# GongKong.net
KiCad netlist of a schematic drawn in Altium Designer
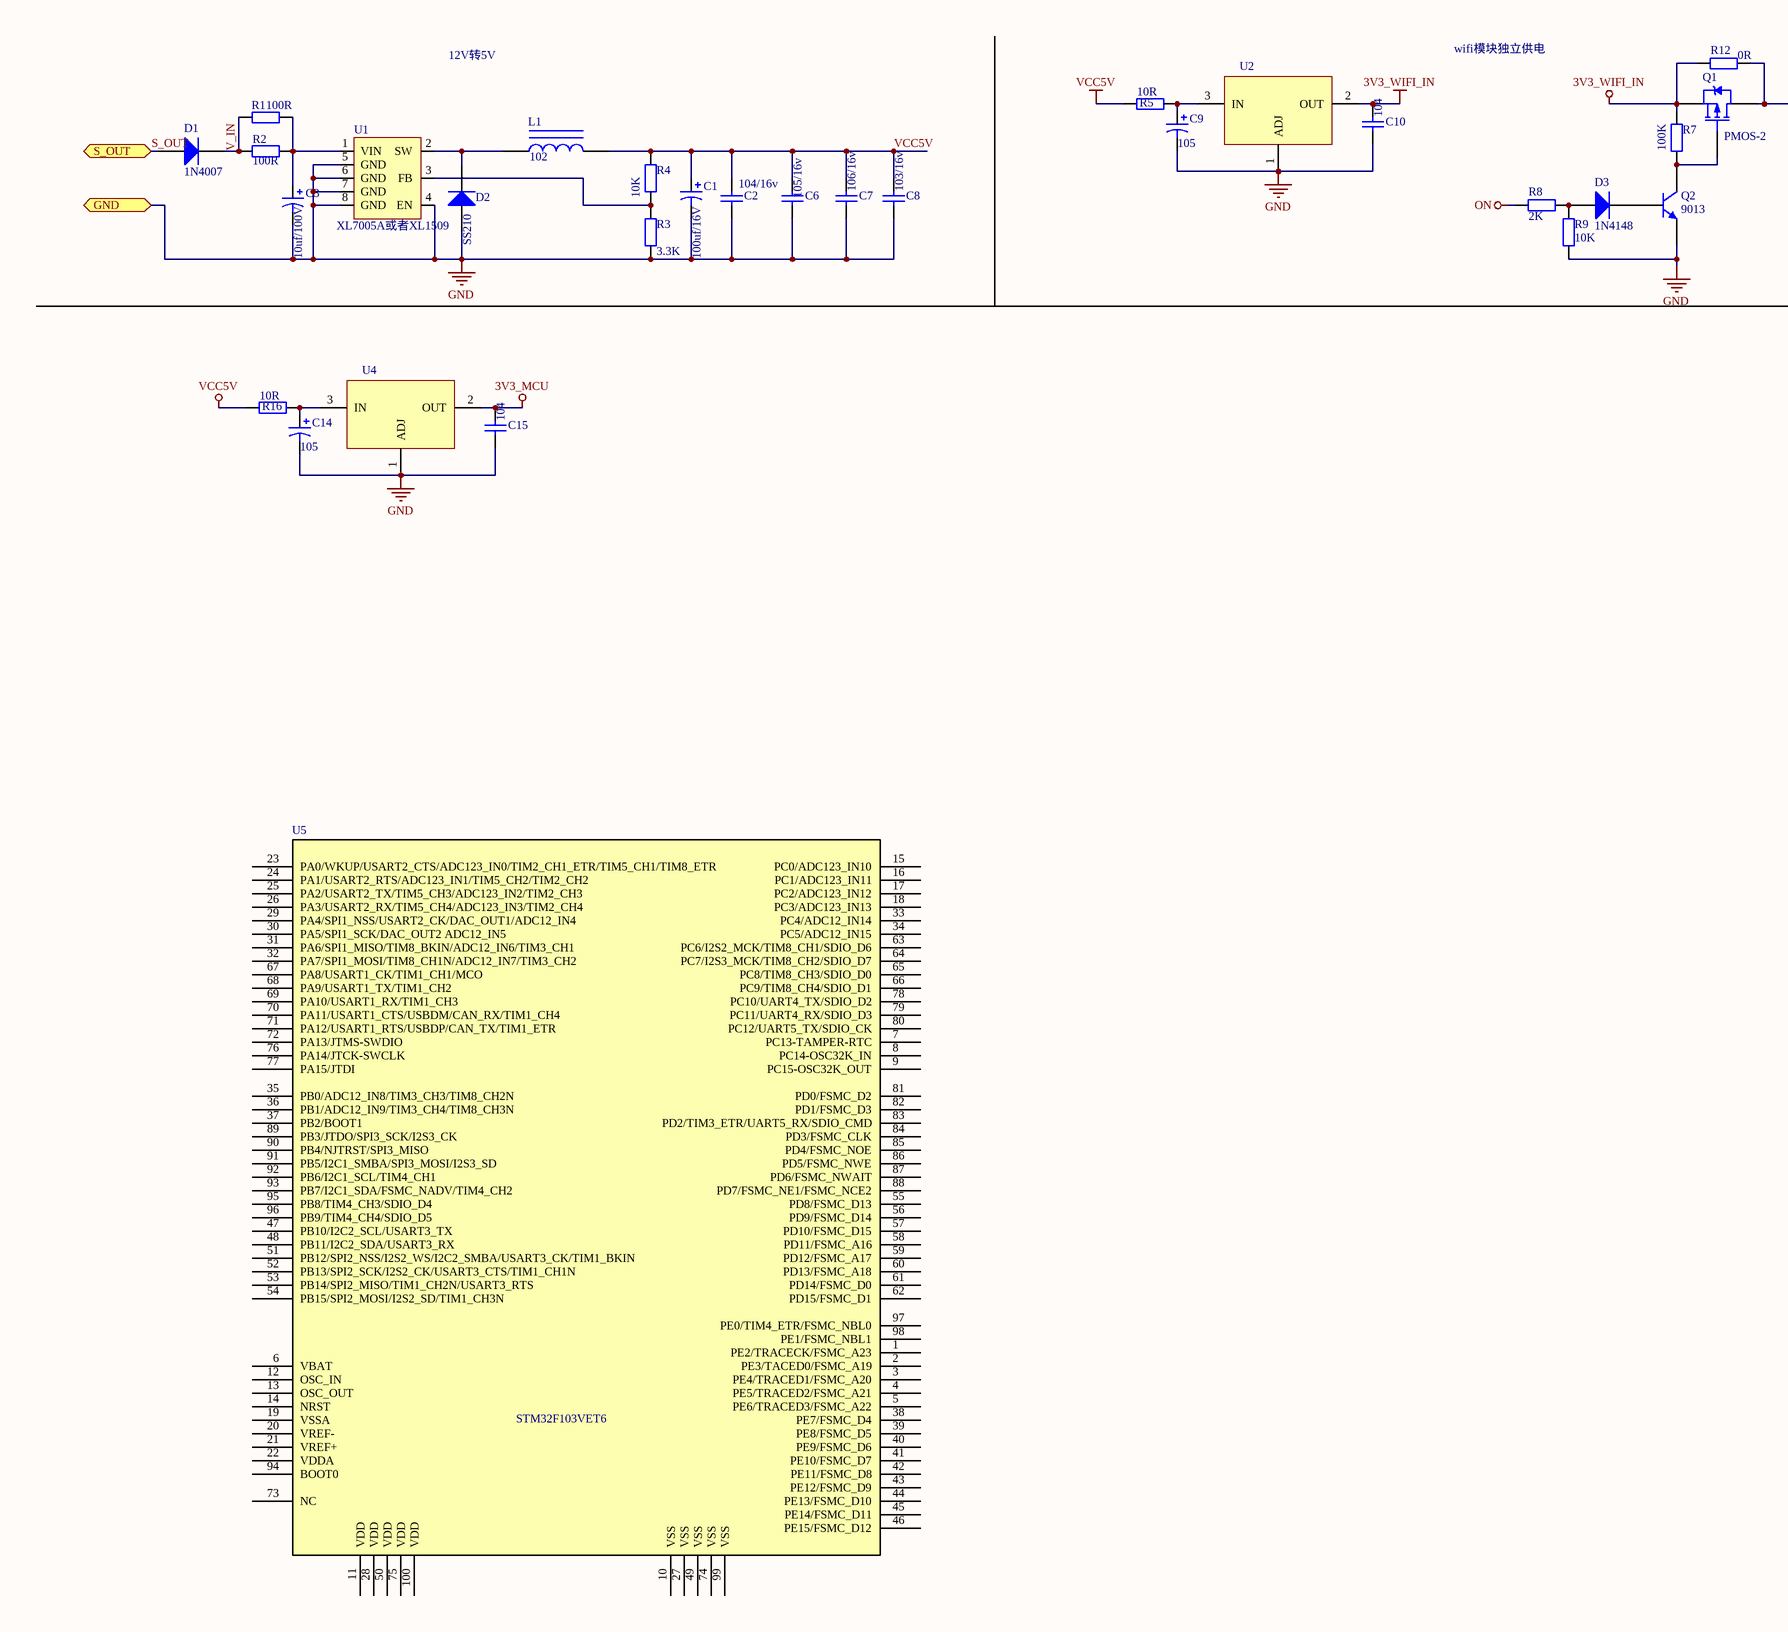
[diagram p0: GongKong.SchDoc, left]
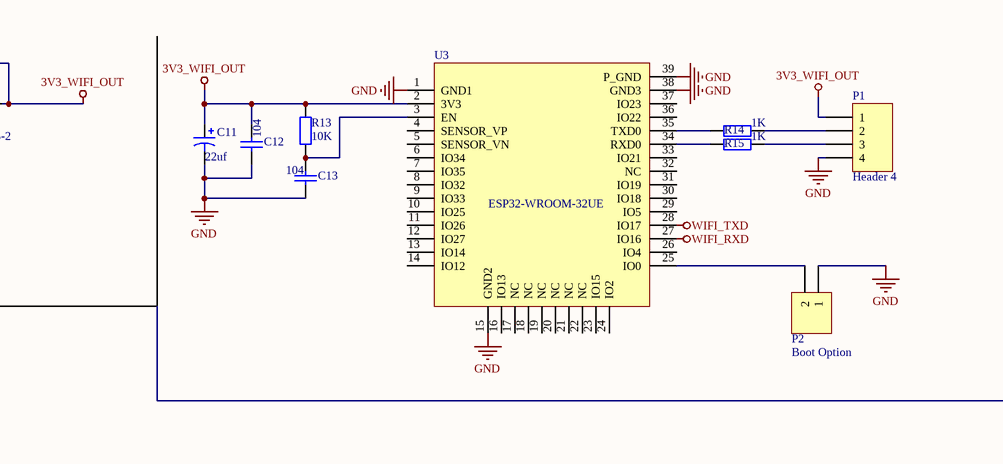
[diagram p1: GongKong.SchDoc, right]

(export (version "E")
  (design (tool "Eeschema 10.0.6"))
  (components
    (comp (ref "C1")
      (value "100uf/16V")
      (footprint "封装:47uf/25V")
      (description "Polarized Capacitor (Radial)")
      (fields (field (name "Comment") "Cap Pol1") (field (name "PUBLISHER") "Altium Limited"))
      (libsource (lib "Miscellaneous Devices") (part "Cap Pol1"))
    )
    (comp (ref "C2")
      (value "104/16v")
      (footprint "0805-JT")
      (description "Capacitor")
      (fields (field (name "Comment") "Cap") (field (name "PUBLISHER") "Altium Limited"))
      (libsource (lib "Miscellaneous Devices") (part "Cap"))
    )
    (comp (ref "C3")
      (value "10uf/100V")
      (footprint "封装:47uf/25V")
      (description "Polarized Capacitor (Radial)")
      (fields (field (name "Comment") "Cap Pol1") (field (name "PUBLISHER") "Altium Limited"))
      (libsource (lib "Miscellaneous Devices") (part "Cap Pol1"))
    )
    (comp (ref "C6")
      (value "105/16v")
      (footprint "0805-JT")
      (description "Capacitor")
      (fields (field (name "Comment") "Cap") (field (name "PUBLISHER") "Altium Limited"))
      (libsource (lib "Miscellaneous Devices") (part "Cap"))
    )
    (comp (ref "C7")
      (value "106/16v")
      (footprint "0805-JT")
      (description "Capacitor")
      (fields (field (name "Comment") "Cap") (field (name "PUBLISHER") "Altium Limited"))
      (libsource (lib "Miscellaneous Devices") (part "Cap"))
    )
    (comp (ref "C8")
      (value "103/16v")
      (footprint "0805-JT")
      (description "Capacitor")
      (fields (field (name "Comment") "Cap") (field (name "PUBLISHER") "Altium Limited"))
      (libsource (lib "Miscellaneous Devices") (part "Cap"))
    )
    (comp (ref "C9")
      (value "105")
      (footprint "RB7.6-15")
      (description "Polarized Capacitor (Radial)")
      (fields (field (name "Comment") "Cap Pol1") (field (name "PUBLISHER") "Altium Limited"))
      (libsource (lib "Miscellaneous Devices") (part "Cap Pol1"))
    )
    (comp (ref "C10")
      (value "104")
      (footprint "0805-JT")
      (description "Capacitor")
      (fields (field (name "Comment") "Cap") (field (name "PUBLISHER") "Altium Limited"))
      (libsource (lib "Miscellaneous Devices") (part "Cap"))
    )
    (comp (ref "C11")
      (value "22uf")
      (footprint "RB7.6-15")
      (description "Polarized Capacitor (Radial)")
      (fields (field (name "Comment") "Cap Pol1") (field (name "PUBLISHER") "Altium Limited"))
      (libsource (lib "Miscellaneous Devices") (part "Cap Pol1"))
    )
    (comp (ref "C12")
      (value "104")
      (footprint "0805-JT")
      (description "Capacitor")
      (fields (field (name "Comment") "Cap") (field (name "PUBLISHER") "Altium Limited"))
      (libsource (lib "Miscellaneous Devices") (part "Cap"))
    )
    (comp (ref "C13")
      (value "104")
      (footprint "0805-JT")
      (description "Capacitor")
      (fields (field (name "Comment") "Cap") (field (name "PUBLISHER") "Altium Limited"))
      (libsource (lib "Miscellaneous Devices") (part "Cap"))
    )
    (comp (ref "C14")
      (value "105")
      (footprint "RB7.6-15")
      (description "Polarized Capacitor (Radial)")
      (fields (field (name "Comment") "Cap Pol1") (field (name "PUBLISHER") "Altium Limited"))
      (libsource (lib "Miscellaneous Devices") (part "Cap Pol1"))
    )
    (comp (ref "C15")
      (value "104")
      (footprint "0805-JT")
      (description "Capacitor")
      (fields (field (name "Comment") "Cap") (field (name "PUBLISHER") "Altium Limited"))
      (libsource (lib "Miscellaneous Devices") (part "Cap"))
    )
    (comp (ref "D1")
      (value "1N4007")
      (footprint "M7 - WX")
      (description "High Conductance Fast Diode")
      (fields (field (name "PUBLISHER") "Altium Limited"))
      (libsource (lib "Miscellaneous Devices") (part "Diode 1N4148"))
    )
    (comp (ref "D2")
      (value "SS210")
      (footprint "M7 - WX")
      (description "High Conductance Fast Diode")
      (fields (field (name "PUBLISHER") "Altium Limited"))
      (libsource (lib "Miscellaneous Devices") (part "Diode 1N4148"))
    )
    (comp (ref "D3")
      (value "1N4148")
      (footprint "SMC")
      (description "Default Diode")
      (fields (field (name "PUBLISHER") "Altium Limited"))
      (libsource (lib "Miscellaneous Devices") (part "Diode"))
    )
    (comp (ref "L1")
      (value "102")
      (footprint "CD54")
      (description "Magnetic-Core Inductor")
      (fields (field (name "Comment") "Inductor Iron") (field (name "PUBLISHER") "Altium Limited"))
      (libsource (lib "Miscellaneous Devices") (part "Inductor Iron"))
    )
    (comp (ref "P1")
      (value "Header 4")
      (footprint "HDR1X4")
      (description "Header, 4-Pin")
      (fields (field (name "PUBLISHER") "Altium Limited"))
      (libsource (lib "Miscellaneous Connectors") (part "Header 4"))
    )
    (comp (ref "P2")
      (value "Boot Option")
      (footprint "HDR1X2")
      (description "Header, 2-Pin")
      (fields (field (name "PUBLISHER") "Altium Limited"))
      (libsource (lib "Miscellaneous Connectors") (part "Header 2"))
    )
    (comp (ref "Q1")
      (value "PMOS-2")
      (footprint "TO-220AB")
      (description "P-Channel Power MOSFET")
      (fields (field (name "PUBLISHER") "Altium Limited"))
      (libsource (lib "Miscellaneous Devices") (part "PMOS-2"))
    )
    (comp (ref "Q2")
      (value "9013")
      (footprint "TO-226-AA")
      (description "NPN Bipolar Transistor")
      (fields (field (name "PUBLISHER") "Altium Limited"))
      (libsource (lib "Miscellaneous Devices") (part "NPN"))
    )
    (comp (ref "R1")
      (value "100R")
      (footprint "1206")
      (description "Resistor")
      (fields (field (name "Comment") "Res2") (field (name "PUBLISHER") "Altium Limited"))
      (libsource (lib "Miscellaneous Devices") (part "Res2"))
    )
    (comp (ref "R2")
      (value "100R")
      (footprint "1206")
      (description "Resistor")
      (fields (field (name "Comment") "Res2") (field (name "PUBLISHER") "Altium Limited"))
      (libsource (lib "Miscellaneous Devices") (part "Res2"))
    )
    (comp (ref "R3")
      (value "3.3K")
      (footprint "0603-JT")
      (description "Resistor")
      (fields (field (name "Comment") "Res2") (field (name "PUBLISHER") "Altium Limited"))
      (libsource (lib "") (part "Res2_1"))
    )
    (comp (ref "R4")
      (value "10K")
      (footprint "0603-JT")
      (description "Resistor")
      (fields (field (name "Comment") "Res2") (field (name "PUBLISHER") "Altium Limited"))
      (libsource (lib "") (part "Res2_1"))
    )
    (comp (ref "R5")
      (value "10R")
      (footprint "1206")
      (description "Resistor")
      (fields (field (name "Comment") "Res2") (field (name "PUBLISHER") "Altium Limited"))
      (libsource (lib "Miscellaneous Devices") (part "Res2"))
    )
    (comp (ref "R7")
      (value "100K")
      (footprint "0603-JT")
      (description "Resistor")
      (fields (field (name "Comment") "Res2") (field (name "PUBLISHER") "Altium Limited"))
      (libsource (lib "") (part "Res2_1"))
    )
    (comp (ref "R8")
      (value "2K")
      (footprint "0603-JT")
      (description "Resistor")
      (fields (field (name "Comment") "Res2") (field (name "PUBLISHER") "Altium Limited"))
      (libsource (lib "Miscellaneous Devices") (part "Res2"))
    )
    (comp (ref "R9")
      (value "10K")
      (footprint "0603-JT")
      (description "Resistor")
      (fields (field (name "Comment") "Res2") (field (name "PUBLISHER") "Altium Limited"))
      (libsource (lib "") (part "Res2_2"))
    )
    (comp (ref "R12")
      (value "0R")
      (footprint "0603-JT")
      (description "Resistor")
      (fields (field (name "Comment") "Res2") (field (name "PUBLISHER") "Altium Limited"))
      (libsource (lib "") (part "Res2_3"))
    )
    (comp (ref "R13")
      (value "10K")
      (footprint "0603-JT")
      (description "Resistor")
      (fields (field (name "Comment") "Res2") (field (name "PUBLISHER") "Altium Limited"))
      (libsource (lib "") (part "Res2_1"))
    )
    (comp (ref "R14")
      (value "1K")
      (footprint "0603-JT")
      (description "Resistor")
      (fields (field (name "Comment") "Res2") (field (name "PUBLISHER") "Altium Limited"))
      (libsource (lib "Miscellaneous Devices") (part "Res2"))
    )
    (comp (ref "R15")
      (value "1K")
      (footprint "0603-JT")
      (description "Resistor")
      (fields (field (name "Comment") "Res2") (field (name "PUBLISHER") "Altium Limited"))
      (libsource (lib "Miscellaneous Devices") (part "Res2"))
    )
    (comp (ref "R16")
      (value "10R")
      (footprint "1206")
      (description "Resistor")
      (fields (field (name "Comment") "Res2") (field (name "PUBLISHER") "Altium Limited"))
      (libsource (lib "Miscellaneous Devices") (part "Res2"))
    )
    (comp (ref "U1") (value "XL7005A或者XL1509") (footprint "SOP8") (libsource (lib "原理图库") (part "XL7005")))
    (comp (ref "U2")
      (value "1117_3V3")
      (footprint "SOT-223-jt")
      (description "3.3V   LDO芯片")
      (libsource (lib "原理图库") (part "1117_3V3"))
    )
    (comp (ref "U3")
      (value "ESP32-WROOM-32UE")
      (description "ESP32 wifi模块 IPEX接口天线")
      (libsource (lib "原理图库") (part "ESP32-WROOM-32UE"))
    )
    (comp (ref "U4")
      (value "1117_3V3")
      (footprint "SOT-223-jt")
      (description "3.3V   LDO芯片")
      (libsource (lib "原理图库") (part "1117_3V3"))
    )
    (comp (ref "U5")
      (value "STM32F103VET6")
      (footprint "LQFP-100")
      (libsource (lib "原理图库") (part "STM32F103VET"))
    )
  )
  (nets
    (net (code "1") (name "/S_OUT") (class "Default")
      (node (ref "D1") (pin "1") (pinfunction "A_1") (pintype "passive"))
    )
    (net (code "2") (name "/V_IN") (class "Default")
      (node (ref "D1") (pin "2") (pinfunction "K_2") (pintype "passive"))
      (node (ref "R1") (pin "1") (pinfunction "1_1") (pintype "passive"))
      (node (ref "R2") (pin "1") (pinfunction "1_1") (pintype "passive"))
    )
    (net (code "3") (name "3V3_MCU") (class "Default")
      (node (ref "C15") (pin "2") (pinfunction "2_2") (pintype "passive"))
      (node (ref "U4") (pin "2") (pinfunction "OUT_2") (pintype "passive"))
    )
    (net (code "4") (name "3V3_WIFI_IN") (class "Default")
      (node (ref "C10") (pin "2") (pinfunction "2_2") (pintype "passive"))
      (node (ref "Q1") (pin "3") (pinfunction "S_3") (pintype "passive"))
      (node (ref "R12") (pin "2") (pinfunction "2_2") (pintype "passive"))
      (node (ref "R7") (pin "1") (pinfunction "1_1") (pintype "passive"))
      (node (ref "U2") (pin "2") (pinfunction "OUT_2") (pintype "passive"))
    )
    (net (code "5") (name "3V3_WIFI_OUT") (class "Default")
      (node (ref "C11") (pin "1") (pinfunction "1_1") (pintype "passive"))
      (node (ref "C12") (pin "2") (pinfunction "2_2") (pintype "passive"))
      (node (ref "P1") (pin "1") (pinfunction "1_1") (pintype "passive"))
      (node (ref "Q1") (pin "2") (pinfunction "D_2") (pintype "passive"))
      (node (ref "R12") (pin "1") (pinfunction "1_1") (pintype "passive"))
      (node (ref "R13") (pin "1") (pinfunction "1_1") (pintype "passive"))
      (node (ref "U3") (pin "2") (pinfunction "3V3_2") (pintype "passive"))
    )
    (net (code "6") (name "GND") (class "Default")
      (node (ref "C1") (pin "2") (pinfunction "2_2") (pintype "passive"))
      (node (ref "C10") (pin "1") (pinfunction "1_1") (pintype "passive"))
      (node (ref "C11") (pin "2") (pinfunction "2_2") (pintype "passive"))
      (node (ref "C12") (pin "1") (pinfunction "1_1") (pintype "passive"))
      (node (ref "C13") (pin "1") (pinfunction "1_1") (pintype "passive"))
      (node (ref "C14") (pin "2") (pinfunction "2_2") (pintype "passive"))
      (node (ref "C15") (pin "1") (pinfunction "1_1") (pintype "passive"))
      (node (ref "C2") (pin "1") (pinfunction "1_1") (pintype "passive"))
      (node (ref "C3") (pin "2") (pinfunction "2_2") (pintype "passive"))
      (node (ref "C6") (pin "1") (pinfunction "1_1") (pintype "passive"))
      (node (ref "C7") (pin "1") (pinfunction "1_1") (pintype "passive"))
      (node (ref "C8") (pin "1") (pinfunction "1_1") (pintype "passive"))
      (node (ref "C9") (pin "2") (pinfunction "2_2") (pintype "passive"))
      (node (ref "D2") (pin "1") (pinfunction "A_1") (pintype "passive"))
      (node (ref "P1") (pin "4") (pinfunction "4_4") (pintype "passive"))
      (node (ref "P2") (pin "1") (pinfunction "1_1") (pintype "passive"))
      (node (ref "Q2") (pin "3") (pinfunction "E_3") (pintype "passive"))
      (node (ref "R3") (pin "2") (pinfunction "2_2") (pintype "passive"))
      (node (ref "R9") (pin "1") (pinfunction "1_1") (pintype "passive"))
      (node (ref "U1") (pin "4") (pinfunction "EN_4") (pintype "passive"))
      (node (ref "U1") (pin "5") (pinfunction "GND_5") (pintype "passive"))
      (node (ref "U1") (pin "6") (pinfunction "GND_6") (pintype "passive"))
      (node (ref "U1") (pin "7") (pinfunction "GND_7") (pintype "passive"))
      (node (ref "U1") (pin "8") (pinfunction "GND_8") (pintype "passive"))
      (node (ref "U2") (pin "1") (pinfunction "ADJ_1") (pintype "passive"))
      (node (ref "U3") (pin "1") (pinfunction "GND1_1") (pintype "passive"))
      (node (ref "U3") (pin "15") (pinfunction "GND2_15") (pintype "passive"))
      (node (ref "U3") (pin "38") (pinfunction "GND3_38") (pintype "passive"))
      (node (ref "U3") (pin "39") (pinfunction "P_GND_39") (pintype "passive"))
      (node (ref "U4") (pin "1") (pinfunction "ADJ_1") (pintype "passive"))
    )
    (net (code "7") (name "Net-(D2-K)") (class "Default")
      (node (ref "D2") (pin "2") (pinfunction "K_2") (pintype "passive"))
      (node (ref "L1") (pin "1") (pinfunction "1_1") (pintype "passive"))
      (node (ref "U1") (pin "2") (pinfunction "SW_2") (pintype "passive"))
    )
    (net (code "8") (name "Net-(D3-A)") (class "Default")
      (node (ref "D3") (pin "1") (pinfunction "A_1") (pintype "passive"))
      (node (ref "R8") (pin "2") (pinfunction "2_2") (pintype "passive"))
      (node (ref "R9") (pin "2") (pinfunction "2_2") (pintype "passive"))
    )
    (net (code "9") (name "Net-(D3-K)") (class "Default")
      (node (ref "D3") (pin "2") (pinfunction "K_2") (pintype "passive"))
      (node (ref "Q2") (pin "2") (pinfunction "B_2") (pintype "passive"))
    )
    (net (code "10") (name "Net-(P1-Pad2)") (class "Default")
      (node (ref "P1") (pin "2") (pinfunction "2_2") (pintype "passive"))
      (node (ref "R14") (pin "2") (pinfunction "2_2") (pintype "passive"))
    )
    (net (code "11") (name "Net-(P1-Pad3)") (class "Default")
      (node (ref "P1") (pin "3") (pinfunction "3_3") (pintype "passive"))
      (node (ref "R15") (pin "2") (pinfunction "2_2") (pintype "passive"))
    )
    (net (code "12") (name "Net-(Q1-G)") (class "Default")
      (node (ref "Q1") (pin "1") (pinfunction "G_1") (pintype "passive"))
      (node (ref "Q2") (pin "1") (pinfunction "C_1") (pintype "passive"))
      (node (ref "R7") (pin "2") (pinfunction "2_2") (pintype "passive"))
    )
    (net (code "13") (name "Net-(U1-FB)") (class "Default")
      (node (ref "R3") (pin "1") (pinfunction "1_1") (pintype "passive"))
      (node (ref "R4") (pin "2") (pinfunction "2_2") (pintype "passive"))
      (node (ref "U1") (pin "3") (pinfunction "FB_3") (pintype "passive"))
    )
    (net (code "14") (name "Net-(U1-VIN)") (class "Default")
      (node (ref "C3") (pin "1") (pinfunction "1_1") (pintype "passive"))
      (node (ref "R1") (pin "2") (pinfunction "2_2") (pintype "passive"))
      (node (ref "R2") (pin "2") (pinfunction "2_2") (pintype "passive"))
      (node (ref "U1") (pin "1") (pinfunction "VIN_1") (pintype "passive"))
    )
    (net (code "15") (name "Net-(U2-IN)") (class "Default")
      (node (ref "C9") (pin "1") (pinfunction "1_1") (pintype "passive"))
      (node (ref "R5") (pin "2") (pinfunction "2_2") (pintype "passive"))
      (node (ref "U2") (pin "3") (pinfunction "IN_3") (pintype "passive"))
    )
    (net (code "16") (name "Net-(U3-EN)") (class "Default")
      (node (ref "C13") (pin "2") (pinfunction "2_2") (pintype "passive"))
      (node (ref "R13") (pin "2") (pinfunction "2_2") (pintype "passive"))
      (node (ref "U3") (pin "3") (pinfunction "EN_3") (pintype "passive"))
    )
    (net (code "17") (name "Net-(U3-IO0)") (class "Default")
      (node (ref "P2") (pin "2") (pinfunction "2_2") (pintype "passive"))
      (node (ref "U3") (pin "25") (pinfunction "IO0_25") (pintype "passive"))
    )
    (net (code "18") (name "Net-(U3-RXD0)") (class "Default")
      (node (ref "R15") (pin "1") (pinfunction "1_1") (pintype "passive"))
      (node (ref "U3") (pin "34") (pinfunction "RXD0_34") (pintype "passive"))
    )
    (net (code "19") (name "Net-(U3-TXD0)") (class "Default")
      (node (ref "R14") (pin "1") (pinfunction "1_1") (pintype "passive"))
      (node (ref "U3") (pin "35") (pinfunction "TXD0_35") (pintype "passive"))
    )
    (net (code "20") (name "Net-(U4-IN)") (class "Default")
      (node (ref "C14") (pin "1") (pinfunction "1_1") (pintype "passive"))
      (node (ref "R16") (pin "2") (pinfunction "2_2") (pintype "passive"))
      (node (ref "U4") (pin "3") (pinfunction "IN_3") (pintype "passive"))
    )
    (net (code "21") (name "ON") (class "Default")
      (node (ref "R8") (pin "1") (pinfunction "1_1") (pintype "passive"))
    )
    (net (code "22") (name "VCC5V") (class "Default")
      (node (ref "C1") (pin "1") (pinfunction "1_1") (pintype "passive"))
      (node (ref "C2") (pin "2") (pinfunction "2_2") (pintype "passive"))
      (node (ref "C6") (pin "2") (pinfunction "2_2") (pintype "passive"))
      (node (ref "C7") (pin "2") (pinfunction "2_2") (pintype "passive"))
      (node (ref "C8") (pin "2") (pinfunction "2_2") (pintype "passive"))
      (node (ref "L1") (pin "2") (pinfunction "2_2") (pintype "passive"))
      (node (ref "R16") (pin "1") (pinfunction "1_1") (pintype "passive"))
      (node (ref "R4") (pin "1") (pinfunction "1_1") (pintype "passive"))
      (node (ref "R5") (pin "1") (pinfunction "1_1") (pintype "passive"))
    )
    (net (code "23") (name "WIFI_RXD") (class "Default")
      (node (ref "U3") (pin "27") (pinfunction "IO16_27") (pintype "passive"))
    )
    (net (code "24") (name "WIFI_TXD") (class "Default")
      (node (ref "U3") (pin "28") (pinfunction "IO17_28") (pintype "passive"))
    )
    (net (code "25") (name "unconnected-(U3-IO2-Pad24)") (class "Default")
      (node (ref "U3") (pin "24") (pinfunction "IO2_24") (pintype "passive"))
    )
    (net (code "26") (name "unconnected-(U3-IO4-Pad26)") (class "Default")
      (node (ref "U3") (pin "26") (pinfunction "IO4_26") (pintype "passive"))
    )
    (net (code "27") (name "unconnected-(U3-IO5-Pad29)") (class "Default")
      (node (ref "U3") (pin "29") (pinfunction "IO5_29") (pintype "passive"))
    )
    (net (code "28") (name "unconnected-(U3-IO12-Pad14)") (class "Default")
      (node (ref "U3") (pin "14") (pinfunction "IO12_14") (pintype "passive"))
    )
    (net (code "29") (name "unconnected-(U3-IO13-Pad16)") (class "Default")
      (node (ref "U3") (pin "16") (pinfunction "IO13_16") (pintype "passive"))
    )
    (net (code "30") (name "unconnected-(U3-IO14-Pad13)") (class "Default")
      (node (ref "U3") (pin "13") (pinfunction "IO14_13") (pintype "passive"))
    )
    (net (code "31") (name "unconnected-(U3-IO15-Pad23)") (class "Default")
      (node (ref "U3") (pin "23") (pinfunction "IO15_23") (pintype "passive"))
    )
    (net (code "32") (name "unconnected-(U3-IO18-Pad30)") (class "Default")
      (node (ref "U3") (pin "30") (pinfunction "IO18_30") (pintype "passive"))
    )
    (net (code "33") (name "unconnected-(U3-IO19-Pad31)") (class "Default")
      (node (ref "U3") (pin "31") (pinfunction "IO19_31") (pintype "passive"))
    )
    (net (code "34") (name "unconnected-(U3-IO21-Pad33)") (class "Default")
      (node (ref "U3") (pin "33") (pinfunction "IO21_33") (pintype "passive"))
    )
    (net (code "35") (name "unconnected-(U3-IO22-Pad36)") (class "Default")
      (node (ref "U3") (pin "36") (pinfunction "IO22_36") (pintype "passive"))
    )
    (net (code "36") (name "unconnected-(U3-IO23-Pad37)") (class "Default")
      (node (ref "U3") (pin "37") (pinfunction "IO23_37") (pintype "passive"))
    )
    (net (code "37") (name "unconnected-(U3-IO25-Pad10)") (class "Default")
      (node (ref "U3") (pin "10") (pinfunction "IO25_10") (pintype "passive"))
    )
    (net (code "38") (name "unconnected-(U3-IO26-Pad11)") (class "Default")
      (node (ref "U3") (pin "11") (pinfunction "IO26_11") (pintype "passive"))
    )
    (net (code "39") (name "unconnected-(U3-IO27-Pad12)") (class "Default")
      (node (ref "U3") (pin "12") (pinfunction "IO27_12") (pintype "passive"))
    )
    (net (code "40") (name "unconnected-(U3-IO32-Pad8)") (class "Default")
      (node (ref "U3") (pin "8") (pinfunction "IO32_8") (pintype "passive"))
    )
    (net (code "41") (name "unconnected-(U3-IO33-Pad9)") (class "Default")
      (node (ref "U3") (pin "9") (pinfunction "IO33_9") (pintype "passive"))
    )
    (net (code "42") (name "unconnected-(U3-IO34-Pad6)") (class "Default")
      (node (ref "U3") (pin "6") (pinfunction "IO34_6") (pintype "passive"))
    )
    (net (code "43") (name "unconnected-(U3-IO35-Pad7)") (class "Default")
      (node (ref "U3") (pin "7") (pinfunction "IO35_7") (pintype "passive"))
    )
    (net (code "44") (name "unconnected-(U3-NC-Pad17)") (class "Default")
      (node (ref "U3") (pin "17") (pinfunction "NC_17") (pintype "passive"))
    )
    (net (code "45") (name "unconnected-(U3-NC-Pad18)") (class "Default")
      (node (ref "U3") (pin "18") (pinfunction "NC_18") (pintype "passive"))
    )
    (net (code "46") (name "unconnected-(U3-NC-Pad19)") (class "Default")
      (node (ref "U3") (pin "19") (pinfunction "NC_19") (pintype "passive"))
    )
    (net (code "47") (name "unconnected-(U3-NC-Pad20)") (class "Default")
      (node (ref "U3") (pin "20") (pinfunction "NC_20") (pintype "passive"))
    )
    (net (code "48") (name "unconnected-(U3-NC-Pad21)") (class "Default")
      (node (ref "U3") (pin "21") (pinfunction "NC_21") (pintype "passive"))
    )
    (net (code "49") (name "unconnected-(U3-NC-Pad22)") (class "Default")
      (node (ref "U3") (pin "22") (pinfunction "NC_22") (pintype "passive"))
    )
    (net (code "50") (name "unconnected-(U3-NC-Pad32)") (class "Default")
      (node (ref "U3") (pin "32") (pinfunction "NC_32") (pintype "passive"))
    )
    (net (code "51") (name "unconnected-(U3-SENSOR_VN-Pad5)") (class "Default")
      (node (ref "U3") (pin "5") (pinfunction "SENSOR_VN_5") (pintype "passive"))
    )
    (net (code "52") (name "unconnected-(U3-SENSOR_VP-Pad4)") (class "Default")
      (node (ref "U3") (pin "4") (pinfunction "SENSOR_VP_4") (pintype "passive"))
    )
    (net (code "53") (name "unconnected-(U5-BOOT0-Pad94)") (class "Default")
      (node (ref "U5") (pin "94") (pinfunction "BOOT0_94") (pintype "passive"))
    )
    (net (code "54") (name "unconnected-(U5-NC-Pad73)") (class "Default")
      (node (ref "U5") (pin "73") (pinfunction "NC_73") (pintype "passive"))
    )
    (net (code "55") (name "unconnected-(U5-NRST-Pad14)") (class "Default")
      (node (ref "U5") (pin "14") (pinfunction "NRST_14") (pintype "passive"))
    )
    (net (code "56") (name "unconnected-(U5-OSC_IN-Pad12)") (class "Default")
      (node (ref "U5") (pin "12") (pinfunction "OSC_IN_12") (pintype "passive"))
    )
    (net (code "57") (name "unconnected-(U5-OSC_OUT-Pad13)") (class "Default")
      (node (ref "U5") (pin "13") (pinfunction "OSC_OUT_13") (pintype "passive"))
    )
    (net (code "58") (name "unconnected-(U5-PA0{slash}WKUP{slash}USART2_CTS{slash}ADC123_IN0{slash}TIM2_CH1_ETR{slash}TIM5_CH1{slash}TIM8_ETR-Pad23)") (class "Default")
      (node (ref "U5") (pin "23") (pinfunction "PA0/WKUP/USART2_CTS/ADC123_IN0/TIM2_CH1_ETR/TIM5_CH1/TIM8_ETR_23") (pintype "passive"))
    )
    (net (code "59") (name "unconnected-(U5-PA1{slash}USART2_RTS{slash}ADC123_IN1{slash}TIM5_CH2{slash}TIM2_CH2-Pad24)") (class "Default")
      (node (ref "U5") (pin "24") (pinfunction "PA1/USART2_RTS/ADC123_IN1/TIM5_CH2/TIM2_CH2_24") (pintype "passive"))
    )
    (net (code "60") (name "unconnected-(U5-PA2{slash}USART2_TX{slash}TIM5_CH3{slash}ADC123_IN2{slash}TIM2_CH3-Pad25)") (class "Default")
      (node (ref "U5") (pin "25") (pinfunction "PA2/USART2_TX/TIM5_CH3/ADC123_IN2/TIM2_CH3_25") (pintype "passive"))
    )
    (net (code "61") (name "unconnected-(U5-PA3{slash}USART2_RX{slash}TIM5_CH4{slash}ADC123_IN3{slash}TIM2_CH4-Pad26)") (class "Default")
      (node (ref "U5") (pin "26") (pinfunction "PA3/USART2_RX/TIM5_CH4/ADC123_IN3/TIM2_CH4_26") (pintype "passive"))
    )
    (net (code "62") (name "unconnected-(U5-PA4{slash}SPI1_NSS{slash}USART2_CK{slash}DAC_OUT1{slash}ADC12_IN4-Pad29)") (class "Default")
      (node (ref "U5") (pin "29") (pinfunction "PA4/SPI1_NSS/USART2_CK/DAC_OUT1/ADC12_IN4_29") (pintype "passive"))
    )
    (net (code "63") (name "unconnected-(U5-PA5{slash}SPI1_SCK{slash}DAC_OUT2_ADC12_IN5-Pad30)") (class "Default")
      (node (ref "U5") (pin "30") (pinfunction "PA5/SPI1_SCK/DAC_OUT2_ADC12_IN5_30") (pintype "passive"))
    )
    (net (code "64") (name "unconnected-(U5-PA6{slash}SPI1_MISO{slash}TIM8_BKIN{slash}ADC12_IN6{slash}TIM3_CH1-Pad31)") (class "Default")
      (node (ref "U5") (pin "31") (pinfunction "PA6/SPI1_MISO/TIM8_BKIN/ADC12_IN6/TIM3_CH1_31") (pintype "passive"))
    )
    (net (code "65") (name "unconnected-(U5-PA7{slash}SPI1_MOSI{slash}TIM8_CH1N{slash}ADC12_IN7{slash}TIM3_CH2-Pad32)") (class "Default")
      (node (ref "U5") (pin "32") (pinfunction "PA7/SPI1_MOSI/TIM8_CH1N/ADC12_IN7/TIM3_CH2_32") (pintype "passive"))
    )
    (net (code "66") (name "unconnected-(U5-PA8{slash}USART1_CK{slash}TIM1_CH1{slash}MCO-Pad67)") (class "Default")
      (node (ref "U5") (pin "67") (pinfunction "PA8/USART1_CK/TIM1_CH1/MCO_67") (pintype "passive"))
    )
    (net (code "67") (name "unconnected-(U5-PA9{slash}USART1_TX{slash}TIM1_CH2-Pad68)") (class "Default")
      (node (ref "U5") (pin "68") (pinfunction "PA9/USART1_TX/TIM1_CH2_68") (pintype "passive"))
    )
    (net (code "68") (name "unconnected-(U5-PA10{slash}USART1_RX{slash}TIM1_CH3-Pad69)") (class "Default")
      (node (ref "U5") (pin "69") (pinfunction "PA10/USART1_RX/TIM1_CH3_69") (pintype "passive"))
    )
    (net (code "69") (name "unconnected-(U5-PA11{slash}USART1_CTS{slash}USBDM{slash}CAN_RX{slash}TIM1_CH4-Pad70)") (class "Default")
      (node (ref "U5") (pin "70") (pinfunction "PA11/USART1_CTS/USBDM/CAN_RX/TIM1_CH4_70") (pintype "passive"))
    )
    (net (code "70") (name "unconnected-(U5-PA12{slash}USART1_RTS{slash}USBDP{slash}CAN_TX{slash}TIM1_ETR-Pad71)") (class "Default")
      (node (ref "U5") (pin "71") (pinfunction "PA12/USART1_RTS/USBDP/CAN_TX/TIM1_ETR_71") (pintype "passive"))
    )
    (net (code "71") (name "unconnected-(U5-PA13{slash}JTMS-SWDIO-Pad72)") (class "Default")
      (node (ref "U5") (pin "72") (pinfunction "PA13/JTMS-SWDIO_72") (pintype "passive"))
    )
    (net (code "72") (name "unconnected-(U5-PA14{slash}JTCK-SWCLK-Pad76)") (class "Default")
      (node (ref "U5") (pin "76") (pinfunction "PA14/JTCK-SWCLK_76") (pintype "passive"))
    )
    (net (code "73") (name "unconnected-(U5-PA15{slash}JTDI-Pad77)") (class "Default")
      (node (ref "U5") (pin "77") (pinfunction "PA15/JTDI_77") (pintype "passive"))
    )
    (net (code "74") (name "unconnected-(U5-PB0{slash}ADC12_IN8{slash}TIM3_CH3{slash}TIM8_CH2N-Pad35)") (class "Default")
      (node (ref "U5") (pin "35") (pinfunction "PB0/ADC12_IN8/TIM3_CH3/TIM8_CH2N_35") (pintype "passive"))
    )
    (net (code "75") (name "unconnected-(U5-PB1{slash}ADC12_IN9{slash}TIM3_CH4{slash}TIM8_CH3N-Pad36)") (class "Default")
      (node (ref "U5") (pin "36") (pinfunction "PB1/ADC12_IN9/TIM3_CH4/TIM8_CH3N_36") (pintype "passive"))
    )
    (net (code "76") (name "unconnected-(U5-PB2{slash}BOOT1-Pad37)") (class "Default")
      (node (ref "U5") (pin "37") (pinfunction "PB2/BOOT1_37") (pintype "passive"))
    )
    (net (code "77") (name "unconnected-(U5-PB3{slash}JTDO{slash}SPI3_SCK{slash}I2S3_CK-Pad89)") (class "Default")
      (node (ref "U5") (pin "89") (pinfunction "PB3/JTDO/SPI3_SCK/I2S3_CK_89") (pintype "passive"))
    )
    (net (code "78") (name "unconnected-(U5-PB4{slash}NJTRST{slash}SPI3_MISO-Pad90)") (class "Default")
      (node (ref "U5") (pin "90") (pinfunction "PB4/NJTRST/SPI3_MISO_90") (pintype "passive"))
    )
    (net (code "79") (name "unconnected-(U5-PB5{slash}I2C1_SMBA{slash}SPI3_MOSI{slash}I2S3_SD-Pad91)") (class "Default")
      (node (ref "U5") (pin "91") (pinfunction "PB5/I2C1_SMBA/SPI3_MOSI/I2S3_SD_91") (pintype "passive"))
    )
    (net (code "80") (name "unconnected-(U5-PB6{slash}I2C1_SCL{slash}TIM4_CH1-Pad92)") (class "Default")
      (node (ref "U5") (pin "92") (pinfunction "PB6/I2C1_SCL/TIM4_CH1_92") (pintype "passive"))
    )
    (net (code "81") (name "unconnected-(U5-PB7{slash}I2C1_SDA{slash}FSMC_NADV{slash}TIM4_CH2-Pad93)") (class "Default")
      (node (ref "U5") (pin "93") (pinfunction "PB7/I2C1_SDA/FSMC_NADV/TIM4_CH2_93") (pintype "passive"))
    )
    (net (code "82") (name "unconnected-(U5-PB8{slash}TIM4_CH3{slash}SDIO_D4-Pad95)") (class "Default")
      (node (ref "U5") (pin "95") (pinfunction "PB8/TIM4_CH3/SDIO_D4_95") (pintype "passive"))
    )
    (net (code "83") (name "unconnected-(U5-PB9{slash}TIM4_CH4{slash}SDIO_D5-Pad96)") (class "Default")
      (node (ref "U5") (pin "96") (pinfunction "PB9/TIM4_CH4/SDIO_D5_96") (pintype "passive"))
    )
    (net (code "84") (name "unconnected-(U5-PB10{slash}I2C2_SCL{slash}USART3_TX-Pad47)") (class "Default")
      (node (ref "U5") (pin "47") (pinfunction "PB10/I2C2_SCL/USART3_TX_47") (pintype "passive"))
    )
    (net (code "85") (name "unconnected-(U5-PB11{slash}I2C2_SDA{slash}USART3_RX-Pad48)") (class "Default")
      (node (ref "U5") (pin "48") (pinfunction "PB11/I2C2_SDA/USART3_RX_48") (pintype "passive"))
    )
    (net (code "86") (name "unconnected-(U5-PB12{slash}SPI2_NSS{slash}I2S2_WS{slash}I2C2_SMBA{slash}USART3_CK{slash}TIM1_BKIN-Pad51)") (class "Default")
      (node (ref "U5") (pin "51") (pinfunction "PB12/SPI2_NSS/I2S2_WS/I2C2_SMBA/USART3_CK/TIM1_BKIN_51") (pintype "passive"))
    )
    (net (code "87") (name "unconnected-(U5-PB13{slash}SPI2_SCK{slash}I2S2_CK{slash}USART3_CTS{slash}TIM1_CH1N-Pad52)") (class "Default")
      (node (ref "U5") (pin "52") (pinfunction "PB13/SPI2_SCK/I2S2_CK/USART3_CTS/TIM1_CH1N_52") (pintype "passive"))
    )
    (net (code "88") (name "unconnected-(U5-PB14{slash}SPI2_MISO{slash}TIM1_CH2N{slash}USART3_RTS-Pad53)") (class "Default")
      (node (ref "U5") (pin "53") (pinfunction "PB14/SPI2_MISO/TIM1_CH2N/USART3_RTS_53") (pintype "passive"))
    )
    (net (code "89") (name "unconnected-(U5-PB15{slash}SPI2_MOSI{slash}I2S2_SD{slash}TIM1_CH3N-Pad54)") (class "Default")
      (node (ref "U5") (pin "54") (pinfunction "PB15/SPI2_MOSI/I2S2_SD/TIM1_CH3N_54") (pintype "passive"))
    )
    (net (code "90") (name "unconnected-(U5-PC0{slash}ADC123_IN10-Pad15)") (class "Default")
      (node (ref "U5") (pin "15") (pinfunction "PC0/ADC123_IN10_15") (pintype "passive"))
    )
    (net (code "91") (name "unconnected-(U5-PC1{slash}ADC123_IN11-Pad16)") (class "Default")
      (node (ref "U5") (pin "16") (pinfunction "PC1/ADC123_IN11_16") (pintype "passive"))
    )
    (net (code "92") (name "unconnected-(U5-PC2{slash}ADC123_IN12-Pad17)") (class "Default")
      (node (ref "U5") (pin "17") (pinfunction "PC2/ADC123_IN12_17") (pintype "passive"))
    )
    (net (code "93") (name "unconnected-(U5-PC3{slash}ADC123_IN13-Pad18)") (class "Default")
      (node (ref "U5") (pin "18") (pinfunction "PC3/ADC123_IN13_18") (pintype "passive"))
    )
    (net (code "94") (name "unconnected-(U5-PC4{slash}ADC12_IN14-Pad33)") (class "Default")
      (node (ref "U5") (pin "33") (pinfunction "PC4/ADC12_IN14_33") (pintype "passive"))
    )
    (net (code "95") (name "unconnected-(U5-PC5{slash}ADC12_IN15-Pad34)") (class "Default")
      (node (ref "U5") (pin "34") (pinfunction "PC5/ADC12_IN15_34") (pintype "passive"))
    )
    (net (code "96") (name "unconnected-(U5-PC6{slash}I2S2_MCK{slash}TIM8_CH1{slash}SDIO_D6-Pad63)") (class "Default")
      (node (ref "U5") (pin "63") (pinfunction "PC6/I2S2_MCK/TIM8_CH1/SDIO_D6_63") (pintype "passive"))
    )
    (net (code "97") (name "unconnected-(U5-PC7{slash}I2S3_MCK{slash}TIM8_CH2{slash}SDIO_D7-Pad64)") (class "Default")
      (node (ref "U5") (pin "64") (pinfunction "PC7/I2S3_MCK/TIM8_CH2/SDIO_D7_64") (pintype "passive"))
    )
    (net (code "98") (name "unconnected-(U5-PC8{slash}TIM8_CH3{slash}SDIO_D0-Pad65)") (class "Default")
      (node (ref "U5") (pin "65") (pinfunction "PC8/TIM8_CH3/SDIO_D0_65") (pintype "passive"))
    )
    (net (code "99") (name "unconnected-(U5-PC9{slash}TIM8_CH4{slash}SDIO_D1-Pad66)") (class "Default")
      (node (ref "U5") (pin "66") (pinfunction "PC9/TIM8_CH4/SDIO_D1_66") (pintype "passive"))
    )
    (net (code "100") (name "unconnected-(U5-PC10{slash}UART4_TX{slash}SDIO_D2-Pad78)") (class "Default")
      (node (ref "U5") (pin "78") (pinfunction "PC10/UART4_TX/SDIO_D2_78") (pintype "passive"))
    )
    (net (code "101") (name "unconnected-(U5-PC11{slash}UART4_RX{slash}SDIO_D3-Pad79)") (class "Default")
      (node (ref "U5") (pin "79") (pinfunction "PC11/UART4_RX/SDIO_D3_79") (pintype "passive"))
    )
    (net (code "102") (name "unconnected-(U5-PC12{slash}UART5_TX{slash}SDIO_CK-Pad80)") (class "Default")
      (node (ref "U5") (pin "80") (pinfunction "PC12/UART5_TX/SDIO_CK_80") (pintype "passive"))
    )
    (net (code "103") (name "unconnected-(U5-PC13-TAMPER-RTC-Pad7)") (class "Default")
      (node (ref "U5") (pin "7") (pinfunction "PC13-TAMPER-RTC_7") (pintype "passive"))
    )
    (net (code "104") (name "unconnected-(U5-PC14-OSC32K_IN-Pad8)") (class "Default")
      (node (ref "U5") (pin "8") (pinfunction "PC14-OSC32K_IN_8") (pintype "passive"))
    )
    (net (code "105") (name "unconnected-(U5-PC15-OSC32K_OUT-Pad9)") (class "Default")
      (node (ref "U5") (pin "9") (pinfunction "PC15-OSC32K_OUT_9") (pintype "passive"))
    )
    (net (code "106") (name "unconnected-(U5-PD0{slash}FSMC_D2-Pad81)") (class "Default")
      (node (ref "U5") (pin "81") (pinfunction "PD0/FSMC_D2_81") (pintype "passive"))
    )
    (net (code "107") (name "unconnected-(U5-PD1{slash}FSMC_D3-Pad82)") (class "Default")
      (node (ref "U5") (pin "82") (pinfunction "PD1/FSMC_D3_82") (pintype "passive"))
    )
    (net (code "108") (name "unconnected-(U5-PD2{slash}TIM3_ETR{slash}UART5_RX{slash}SDIO_CMD-Pad83)") (class "Default")
      (node (ref "U5") (pin "83") (pinfunction "PD2/TIM3_ETR/UART5_RX/SDIO_CMD_83") (pintype "passive"))
    )
    (net (code "109") (name "unconnected-(U5-PD3{slash}FSMC_CLK-Pad84)") (class "Default")
      (node (ref "U5") (pin "84") (pinfunction "PD3/FSMC_CLK_84") (pintype "passive"))
    )
    (net (code "110") (name "unconnected-(U5-PD4{slash}FSMC_NOE-Pad85)") (class "Default")
      (node (ref "U5") (pin "85") (pinfunction "PD4/FSMC_NOE_85") (pintype "passive"))
    )
    (net (code "111") (name "unconnected-(U5-PD5{slash}FSMC_NWE-Pad86)") (class "Default")
      (node (ref "U5") (pin "86") (pinfunction "PD5/FSMC_NWE_86") (pintype "passive"))
    )
    (net (code "112") (name "unconnected-(U5-PD6{slash}FSMC_NWAIT-Pad87)") (class "Default")
      (node (ref "U5") (pin "87") (pinfunction "PD6/FSMC_NWAIT_87") (pintype "passive"))
    )
    (net (code "113") (name "unconnected-(U5-PD7{slash}FSMC_NE1{slash}FSMC_NCE2-Pad88)") (class "Default")
      (node (ref "U5") (pin "88") (pinfunction "PD7/FSMC_NE1/FSMC_NCE2_88") (pintype "passive"))
    )
    (net (code "114") (name "unconnected-(U5-PD8{slash}FSMC_D13-Pad55)") (class "Default")
      (node (ref "U5") (pin "55") (pinfunction "PD8/FSMC_D13_55") (pintype "passive"))
    )
    (net (code "115") (name "unconnected-(U5-PD9{slash}FSMC_D14-Pad56)") (class "Default")
      (node (ref "U5") (pin "56") (pinfunction "PD9/FSMC_D14_56") (pintype "passive"))
    )
    (net (code "116") (name "unconnected-(U5-PD10{slash}FSMC_D15-Pad57)") (class "Default")
      (node (ref "U5") (pin "57") (pinfunction "PD10/FSMC_D15_57") (pintype "passive"))
    )
    (net (code "117") (name "unconnected-(U5-PD11{slash}FSMC_A16-Pad58)") (class "Default")
      (node (ref "U5") (pin "58") (pinfunction "PD11/FSMC_A16_58") (pintype "passive"))
    )
    (net (code "118") (name "unconnected-(U5-PD12{slash}FSMC_A17-Pad59)") (class "Default")
      (node (ref "U5") (pin "59") (pinfunction "PD12/FSMC_A17_59") (pintype "passive"))
    )
    (net (code "119") (name "unconnected-(U5-PD13{slash}FSMC_A18-Pad60)") (class "Default")
      (node (ref "U5") (pin "60") (pinfunction "PD13/FSMC_A18_60") (pintype "passive"))
    )
    (net (code "120") (name "unconnected-(U5-PD14{slash}FSMC_D0-Pad61)") (class "Default")
      (node (ref "U5") (pin "61") (pinfunction "PD14/FSMC_D0_61") (pintype "passive"))
    )
    (net (code "121") (name "unconnected-(U5-PD15{slash}FSMC_D1-Pad62)") (class "Default")
      (node (ref "U5") (pin "62") (pinfunction "PD15/FSMC_D1_62") (pintype "passive"))
    )
    (net (code "122") (name "unconnected-(U5-PE0{slash}TIM4_ETR{slash}FSMC_NBL0-Pad97)") (class "Default")
      (node (ref "U5") (pin "97") (pinfunction "PE0/TIM4_ETR/FSMC_NBL0_97") (pintype "passive"))
    )
    (net (code "123") (name "unconnected-(U5-PE1{slash}FSMC_NBL1-Pad98)") (class "Default")
      (node (ref "U5") (pin "98") (pinfunction "PE1/FSMC_NBL1_98") (pintype "passive"))
    )
    (net (code "124") (name "unconnected-(U5-PE2{slash}TRACECK{slash}FSMC_A23-Pad1)") (class "Default")
      (node (ref "U5") (pin "1") (pinfunction "PE2/TRACECK/FSMC_A23_1") (pintype "passive"))
    )
    (net (code "125") (name "unconnected-(U5-PE3{slash}TACED0{slash}FSMC_A19-Pad2)") (class "Default")
      (node (ref "U5") (pin "2") (pinfunction "PE3/TACED0/FSMC_A19_2") (pintype "passive"))
    )
    (net (code "126") (name "unconnected-(U5-PE4{slash}TRACED1{slash}FSMC_A20-Pad3)") (class "Default")
      (node (ref "U5") (pin "3") (pinfunction "PE4/TRACED1/FSMC_A20_3") (pintype "passive"))
    )
    (net (code "127") (name "unconnected-(U5-PE5{slash}TRACED2{slash}FSMC_A21-Pad4)") (class "Default")
      (node (ref "U5") (pin "4") (pinfunction "PE5/TRACED2/FSMC_A21_4") (pintype "passive"))
    )
    (net (code "128") (name "unconnected-(U5-PE6{slash}TRACED3{slash}FSMC_A22-Pad5)") (class "Default")
      (node (ref "U5") (pin "5") (pinfunction "PE6/TRACED3/FSMC_A22_5") (pintype "passive"))
    )
    (net (code "129") (name "unconnected-(U5-PE7{slash}FSMC_D4-Pad38)") (class "Default")
      (node (ref "U5") (pin "38") (pinfunction "PE7/FSMC_D4_38") (pintype "passive"))
    )
    (net (code "130") (name "unconnected-(U5-PE8{slash}FSMC_D5-Pad39)") (class "Default")
      (node (ref "U5") (pin "39") (pinfunction "PE8/FSMC_D5_39") (pintype "passive"))
    )
    (net (code "131") (name "unconnected-(U5-PE9{slash}FSMC_D6-Pad40)") (class "Default")
      (node (ref "U5") (pin "40") (pinfunction "PE9/FSMC_D6_40") (pintype "passive"))
    )
    (net (code "132") (name "unconnected-(U5-PE10{slash}FSMC_D7-Pad41)") (class "Default")
      (node (ref "U5") (pin "41") (pinfunction "PE10/FSMC_D7_41") (pintype "passive"))
    )
    (net (code "133") (name "unconnected-(U5-PE11{slash}FSMC_D8-Pad42)") (class "Default")
      (node (ref "U5") (pin "42") (pinfunction "PE11/FSMC_D8_42") (pintype "passive"))
    )
    (net (code "134") (name "unconnected-(U5-PE12{slash}FSMC_D9-Pad43)") (class "Default")
      (node (ref "U5") (pin "43") (pinfunction "PE12/FSMC_D9_43") (pintype "passive"))
    )
    (net (code "135") (name "unconnected-(U5-PE13{slash}FSMC_D10-Pad44)") (class "Default")
      (node (ref "U5") (pin "44") (pinfunction "PE13/FSMC_D10_44") (pintype "passive"))
    )
    (net (code "136") (name "unconnected-(U5-PE14{slash}FSMC_D11-Pad45)") (class "Default")
      (node (ref "U5") (pin "45") (pinfunction "PE14/FSMC_D11_45") (pintype "passive"))
    )
    (net (code "137") (name "unconnected-(U5-PE15{slash}FSMC_D12-Pad46)") (class "Default")
      (node (ref "U5") (pin "46") (pinfunction "PE15/FSMC_D12_46") (pintype "passive"))
    )
    (net (code "138") (name "unconnected-(U5-VBAT-Pad6)") (class "Default")
      (node (ref "U5") (pin "6") (pinfunction "VBAT_6") (pintype "passive"))
    )
    (net (code "139") (name "unconnected-(U5-VDD-Pad11)") (class "Default")
      (node (ref "U5") (pin "11") (pinfunction "VDD_11") (pintype "passive"))
    )
    (net (code "140") (name "unconnected-(U5-VDD-Pad28)") (class "Default")
      (node (ref "U5") (pin "28") (pinfunction "VDD_28") (pintype "passive"))
    )
    (net (code "141") (name "unconnected-(U5-VDD-Pad50)") (class "Default")
      (node (ref "U5") (pin "50") (pinfunction "VDD_50") (pintype "passive"))
    )
    (net (code "142") (name "unconnected-(U5-VDD-Pad75)") (class "Default")
      (node (ref "U5") (pin "75") (pinfunction "VDD_75") (pintype "passive"))
    )
    (net (code "143") (name "unconnected-(U5-VDD-Pad100)") (class "Default")
      (node (ref "U5") (pin "100") (pinfunction "VDD_100") (pintype "passive"))
    )
    (net (code "144") (name "unconnected-(U5-VDDA-Pad22)") (class "Default")
      (node (ref "U5") (pin "22") (pinfunction "VDDA_22") (pintype "passive"))
    )
    (net (code "145") (name "unconnected-(U5-VREF+-Pad21)") (class "Default")
      (node (ref "U5") (pin "21") (pinfunction "VREF+_21") (pintype "passive"))
    )
    (net (code "146") (name "unconnected-(U5-VREF--Pad20)") (class "Default")
      (node (ref "U5") (pin "20") (pinfunction "VREF-_20") (pintype "passive"))
    )
    (net (code "147") (name "unconnected-(U5-VSS-Pad10)") (class "Default")
      (node (ref "U5") (pin "10") (pinfunction "VSS_10") (pintype "passive"))
    )
    (net (code "148") (name "unconnected-(U5-VSS-Pad27)") (class "Default")
      (node (ref "U5") (pin "27") (pinfunction "VSS_27") (pintype "passive"))
    )
    (net (code "149") (name "unconnected-(U5-VSS-Pad49)") (class "Default")
      (node (ref "U5") (pin "49") (pinfunction "VSS_49") (pintype "passive"))
    )
    (net (code "150") (name "unconnected-(U5-VSS-Pad74)") (class "Default")
      (node (ref "U5") (pin "74") (pinfunction "VSS_74") (pintype "passive"))
    )
    (net (code "151") (name "unconnected-(U5-VSS-Pad99)") (class "Default")
      (node (ref "U5") (pin "99") (pinfunction "VSS_99") (pintype "passive"))
    )
    (net (code "152") (name "unconnected-(U5-VSSA-Pad19)") (class "Default")
      (node (ref "U5") (pin "19") (pinfunction "VSSA_19") (pintype "passive"))
    )
  )
)
